# decoder.net
KiCad netlist of a schematic drawn in EAGLE
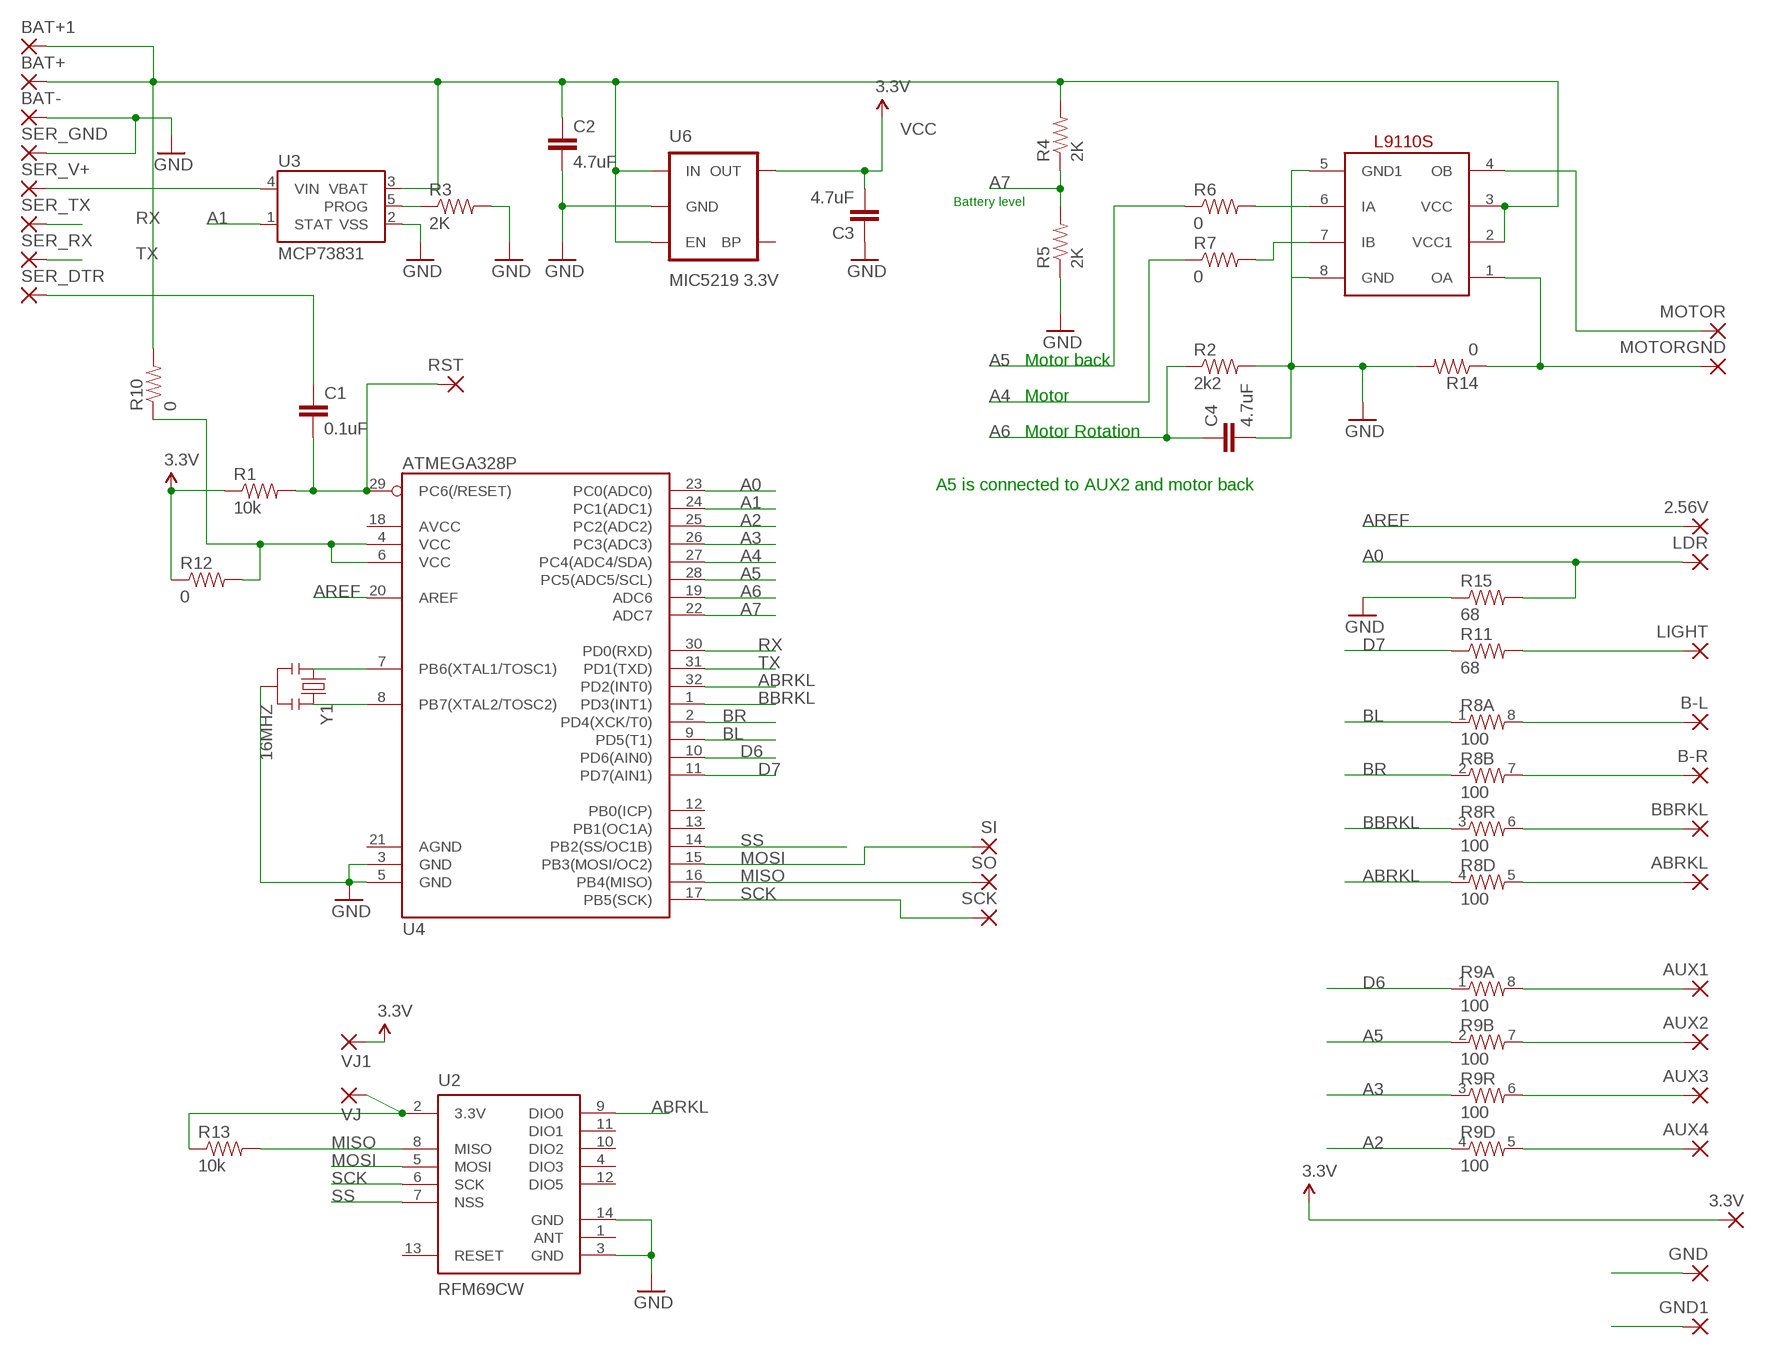
[diagram p0: schematic, sheet 1]

(export (version "E")
  (design (tool "Eeschema 10.0.6"))
  (components
    (comp (ref "2.56V")
      (value "SMD2")
      (footprint "eagle-import:SMD1,27-2,54")
      (libsource (lib "eagle-import") (part "SMD2"))
    )
    (comp (ref "3.3V")
      (value "SMD2")
      (footprint "eagle-import:SMD1,27-2,54")
      (libsource (lib "eagle-import") (part "SMD2"))
    )
    (comp (ref "ABRKL")
      (value "SMD2")
      (footprint "eagle-import:SMD1,27-2,54")
      (libsource (lib "eagle-import") (part "SMD2"))
    )
    (comp (ref "AUX1")
      (value "SMD2")
      (footprint "eagle-import:SMD1,27-2,54")
      (libsource (lib "eagle-import") (part "SMD2"))
    )
    (comp (ref "AUX2")
      (value "SMD2")
      (footprint "eagle-import:SMD1,27-2,54")
      (libsource (lib "eagle-import") (part "SMD2"))
    )
    (comp (ref "AUX3")
      (value "SMD2")
      (footprint "eagle-import:SMD1,27-2,54")
      (libsource (lib "eagle-import") (part "SMD2"))
    )
    (comp (ref "AUX4")
      (value "SMD2")
      (footprint "eagle-import:SMD1,27-2,54")
      (libsource (lib "eagle-import") (part "SMD2"))
    )
    (comp (ref "B-L")
      (value "SMD2")
      (footprint "eagle-import:SMD1,27-2,54")
      (libsource (lib "eagle-import") (part "SMD2"))
    )
    (comp (ref "B-R")
      (value "SMD2")
      (footprint "eagle-import:SMD1,27-2,54")
      (libsource (lib "eagle-import") (part "SMD2"))
    )
    (comp (ref "BAT+")
      (value "SMD2")
      (footprint "eagle-import:SMD1,27-2,54")
      (libsource (lib "eagle-import") (part "SMD2"))
    )
    (comp (ref "BAT+1")
      (value "SMD2")
      (footprint "eagle-import:SMD1,27-2,54")
      (libsource (lib "eagle-import") (part "SMD2"))
    )
    (comp (ref "BAT-")
      (value "SMD2")
      (footprint "eagle-import:SMD1,27-2,54")
      (libsource (lib "eagle-import") (part "SMD2"))
    )
    (comp (ref "BBRKL")
      (value "SMD2")
      (footprint "eagle-import:SMD1,27-2,54")
      (libsource (lib "eagle-import") (part "SMD2"))
    )
    (comp (ref "C1")
      (value "0.1uF")
      (footprint "eagle-import:0805")
      (libsource (lib "eagle-import") (part "CAP0805"))
    )
    (comp (ref "C2")
      (value "4.7uF")
      (footprint "eagle-import:0805")
      (libsource (lib "eagle-import") (part "CAP0805"))
    )
    (comp (ref "C3")
      (value "4.7uF")
      (footprint "eagle-import:0805")
      (libsource (lib "eagle-import") (part "CAP0805"))
    )
    (comp (ref "C4")
      (value "4.7uF")
      (footprint "eagle-import:0805")
      (libsource (lib "eagle-import") (part "CAP0805"))
    )
    (comp (ref "GND")
      (value "SMD2")
      (footprint "eagle-import:SMD1,27-2,54")
      (libsource (lib "eagle-import") (part "SMD2"))
    )
    (comp (ref "GND1")
      (value "SMD2")
      (footprint "eagle-import:SMD1,27-2,54")
      (libsource (lib "eagle-import") (part "SMD2"))
    )
    (comp (ref "LDR")
      (value "SMD2")
      (footprint "eagle-import:SMD1,27-2,54")
      (libsource (lib "eagle-import") (part "SMD2"))
    )
    (comp (ref "LIGHT")
      (value "SMD2")
      (footprint "eagle-import:SMD1,27-2,54")
      (libsource (lib "eagle-import") (part "SMD2"))
    )
    (comp (ref "MDRIVER")
      (value "L9110S")
      (footprint "eagle-import:SO08")
      (libsource (lib "eagle-import") (part "L9110S"))
    )
    (comp (ref "MOTOR")
      (value "SMD2")
      (footprint "eagle-import:SMD1,27-2,54")
      (libsource (lib "eagle-import") (part "SMD2"))
    )
    (comp (ref "MOTORGND")
      (value "SMD2")
      (footprint "eagle-import:SMD1,27-2,54")
      (libsource (lib "eagle-import") (part "SMD2"))
    )
    (comp (ref "R1")
      (value "10k")
      (footprint "eagle-import:0603-RES")
      (libsource (lib "eagle-import") (part "RESISTOR0603-RES"))
    )
    (comp (ref "R2")
      (value "2k2")
      (footprint "eagle-import:0603-RES")
      (libsource (lib "eagle-import") (part "RESISTOR0603-RES"))
    )
    (comp (ref "R3")
      (value "2K")
      (footprint "eagle-import:0603-RES")
      (libsource (lib "eagle-import") (part "RESISTOR0603-RES"))
    )
    (comp (ref "R4")
      (value "2K")
      (footprint "eagle-import:0603-RES")
      (libsource (lib "eagle-import") (part "RESISTOR0603-RES"))
    )
    (comp (ref "R5")
      (value "2K")
      (footprint "eagle-import:0603-RES")
      (libsource (lib "eagle-import") (part "RESISTOR0603-RES"))
    )
    (comp (ref "R6")
      (value "0")
      (footprint "eagle-import:0603-RES")
      (libsource (lib "eagle-import") (part "RESISTOR0603-RES"))
    )
    (comp (ref "R7")
      (value "0")
      (footprint "eagle-import:0603-RES")
      (libsource (lib "eagle-import") (part "RESISTOR0603-RES"))
    )
    (comp (ref "R8")
      (value "100")
      (footprint "eagle-import:0603-ARV")
      (libsource (lib "eagle-import") (part "RESISTOR-ARRAY0603-ARV"))
    )
    (comp (ref "R9")
      (value "100")
      (footprint "eagle-import:0603-ARV")
      (libsource (lib "eagle-import") (part "RESISTOR-ARRAY0603-ARV"))
    )
    (comp (ref "R10")
      (value "0")
      (footprint "eagle-import:0603-RES")
      (libsource (lib "eagle-import") (part "RESISTOR0603-RES"))
    )
    (comp (ref "R11")
      (value "68")
      (footprint "eagle-import:0603-RES")
      (libsource (lib "eagle-import") (part "RESISTOR0603-RES"))
    )
    (comp (ref "R12")
      (value "0")
      (footprint "eagle-import:0603-RES")
      (libsource (lib "eagle-import") (part "RESISTOR0603-RES"))
    )
    (comp (ref "R13")
      (value "10k")
      (footprint "eagle-import:0603-RES")
      (libsource (lib "eagle-import") (part "RESISTOR0603-RES"))
    )
    (comp (ref "R14")
      (value "0")
      (footprint "eagle-import:0603-RES")
      (libsource (lib "eagle-import") (part "RESISTOR0603-RES"))
    )
    (comp (ref "R15")
      (value "68")
      (footprint "eagle-import:0603-RES")
      (libsource (lib "eagle-import") (part "RESISTOR0603-RES"))
    )
    (comp (ref "RST")
      (value "SMD2")
      (footprint "eagle-import:SMD1,27-2,54")
      (libsource (lib "eagle-import") (part "SMD2"))
    )
    (comp (ref "SCK")
      (value "SMD2")
      (footprint "eagle-import:SMD1,27-2,54")
      (libsource (lib "eagle-import") (part "SMD2"))
    )
    (comp (ref "SER_DTR")
      (value "SMD2")
      (footprint "eagle-import:SMD1,27-2,54")
      (libsource (lib "eagle-import") (part "SMD2"))
    )
    (comp (ref "SER_GND")
      (value "SMD2")
      (footprint "eagle-import:SMD1,27-2,54")
      (libsource (lib "eagle-import") (part "SMD2"))
    )
    (comp (ref "SER_RX")
      (value "SMD2")
      (footprint "eagle-import:SMD1,27-2,54")
      (libsource (lib "eagle-import") (part "SMD2"))
    )
    (comp (ref "SER_TX")
      (value "SMD2")
      (footprint "eagle-import:SMD1,27-2,54")
      (libsource (lib "eagle-import") (part "SMD2"))
    )
    (comp (ref "SER_V+")
      (value "SMD2")
      (footprint "eagle-import:SMD1,27-2,54")
      (libsource (lib "eagle-import") (part "SMD2"))
    )
    (comp (ref "SI")
      (value "SMD2")
      (footprint "eagle-import:SMD1,27-2,54")
      (libsource (lib "eagle-import") (part "SMD2"))
    )
    (comp (ref "SO")
      (value "SMD2")
      (footprint "eagle-import:SMD1,27-2,54")
      (libsource (lib "eagle-import") (part "SMD2"))
    )
    (comp (ref "U2")
      (value "RFM69CW")
      (footprint "eagle-import:RFM69CW-XXXS2")
      (libsource (lib "eagle-import") (part "RFM69CW"))
    )
    (comp (ref "U3")
      (value "MCP73831")
      (footprint "eagle-import:SOT23-5")
      (libsource (lib "eagle-import") (part "MCP73831"))
    )
    (comp (ref "U4")
      (value "ATMEGA328P")
      (footprint "eagle-import:TQFP32-08")
      (libsource (lib "eagle-import") (part "ATMEGA328_SMT"))
    )
    (comp (ref "U6")
      (value "MIC5219 3.3V")
      (footprint "eagle-import:SOT23-5")
      (libsource (lib "eagle-import") (part "V_REG_MIC52193.3V"))
    )
    (comp (ref "VJ")
      (value "SMD2")
      (footprint "eagle-import:SMD1,27-2,54")
      (libsource (lib "eagle-import") (part "SMD2"))
    )
    (comp (ref "VJ1")
      (value "SMD2")
      (footprint "eagle-import:SMD1,27-2,54")
      (libsource (lib "eagle-import") (part "SMD2"))
    )
    (comp (ref "Y1")
      (value "16MHZ")
      (footprint "eagle-import:RESONATOR-SMD")
      (libsource (lib "eagle-import") (part "RESONATOR16MHZ"))
    )
  )
  (nets
    (net (code "1") (name "/A0") (class "Default")
      (node (ref "LDR") (pin "1") (pinfunction "P_1") (pintype "passive"))
      (node (ref "R15") (pin "2") (pinfunction "2_2") (pintype "passive"))
      (node (ref "U4") (pin "23") (pinfunction "PC0(ADC0)_23") (pintype "bidirectional"))
    )
    (net (code "2") (name "/A1") (class "Default")
      (node (ref "U3") (pin "1") (pinfunction "STAT_1") (pintype "output"))
      (node (ref "U4") (pin "24") (pinfunction "PC1(ADC1)_24") (pintype "bidirectional"))
    )
    (net (code "3") (name "/A2") (class "Default")
      (node (ref "R9") (pin "4") (pinfunction "1_4") (pintype "passive"))
      (node (ref "U4") (pin "25") (pinfunction "PC2(ADC2)_25") (pintype "bidirectional"))
    )
    (net (code "4") (name "/A3") (class "Default")
      (node (ref "R9") (pin "3") (pinfunction "1_3") (pintype "passive"))
      (node (ref "U4") (pin "26") (pinfunction "PC3(ADC3)_26") (pintype "bidirectional"))
    )
    (net (code "5") (name "/A4") (class "Default")
      (node (ref "R7") (pin "1") (pinfunction "1_1") (pintype "passive"))
      (node (ref "U4") (pin "27") (pinfunction "PC4(ADC4/SDA)_27") (pintype "bidirectional"))
    )
    (net (code "6") (name "/A5") (class "Default")
      (node (ref "R6") (pin "1") (pinfunction "1_1") (pintype "passive"))
      (node (ref "R9") (pin "2") (pinfunction "1_2") (pintype "passive"))
      (node (ref "U4") (pin "28") (pinfunction "PC5(ADC5/SCL)_28") (pintype "bidirectional"))
    )
    (net (code "7") (name "/A6") (class "Default")
      (node (ref "C4") (pin "1") (pinfunction "1_1") (pintype "passive"))
      (node (ref "R2") (pin "1") (pinfunction "1_1") (pintype "passive"))
      (node (ref "U4") (pin "19") (pinfunction "ADC6_19") (pintype "bidirectional"))
    )
    (net (code "8") (name "/A7") (class "Default")
      (node (ref "R4") (pin "1") (pinfunction "1_1") (pintype "passive"))
      (node (ref "R5") (pin "2") (pinfunction "2_2") (pintype "passive"))
      (node (ref "U4") (pin "22") (pinfunction "ADC7_22") (pintype "bidirectional"))
    )
    (net (code "9") (name "/ABRKL") (class "Default")
      (node (ref "R8") (pin "4") (pinfunction "1_4") (pintype "passive"))
      (node (ref "U2") (pin "9") (pinfunction "DIO0_9") (pintype "bidirectional"))
      (node (ref "U4") (pin "32") (pinfunction "PD2(INT0)_32") (pintype "bidirectional"))
    )
    (net (code "10") (name "/AREF") (class "Default")
      (node (ref "2.56V") (pin "1") (pinfunction "P_1") (pintype "passive"))
      (node (ref "U4") (pin "20") (pinfunction "AREF_20") (pintype "bidirectional"))
    )
    (net (code "11") (name "/BBRKL") (class "Default")
      (node (ref "R8") (pin "3") (pinfunction "1_3") (pintype "passive"))
      (node (ref "U4") (pin "1") (pinfunction "PD3(INT1)_1") (pintype "bidirectional"))
    )
    (net (code "12") (name "/BL") (class "Default")
      (node (ref "R8") (pin "1") (pinfunction "1_1") (pintype "passive"))
      (node (ref "U4") (pin "9") (pinfunction "PD5(T1)_9") (pintype "bidirectional"))
    )
    (net (code "13") (name "/BR") (class "Default")
      (node (ref "R8") (pin "2") (pinfunction "1_2") (pintype "passive"))
      (node (ref "U4") (pin "2") (pinfunction "PD4(XCK/T0)_2") (pintype "bidirectional"))
    )
    (net (code "14") (name "/D6") (class "Default")
      (node (ref "R9") (pin "1") (pinfunction "1_1") (pintype "passive"))
      (node (ref "U4") (pin "10") (pinfunction "PD6(AIN0)_10") (pintype "bidirectional"))
    )
    (net (code "15") (name "/D7") (class "Default")
      (node (ref "R11") (pin "1") (pinfunction "1_1") (pintype "passive"))
      (node (ref "U4") (pin "11") (pinfunction "PD7(AIN1)_11") (pintype "bidirectional"))
    )
    (net (code "16") (name "/MISO") (class "Default")
      (node (ref "R13") (pin "2") (pinfunction "2_2") (pintype "passive"))
      (node (ref "SO") (pin "1") (pinfunction "P_1") (pintype "passive"))
      (node (ref "U2") (pin "8") (pinfunction "MISO_8") (pintype "bidirectional"))
      (node (ref "U4") (pin "16") (pinfunction "PB4(MISO)_16") (pintype "bidirectional"))
    )
    (net (code "17") (name "/MOSI") (class "Default")
      (node (ref "SI") (pin "1") (pinfunction "P_1") (pintype "passive"))
      (node (ref "U2") (pin "5") (pinfunction "MOSI_5") (pintype "input"))
      (node (ref "U4") (pin "15") (pinfunction "PB3(MOSI/OC2)_15") (pintype "bidirectional"))
    )
    (net (code "18") (name "/RX") (class "Default")
      (node (ref "SER_TX") (pin "1") (pinfunction "P_1") (pintype "passive"))
      (node (ref "U4") (pin "30") (pinfunction "PD0(RXD)_30") (pintype "bidirectional"))
    )
    (net (code "19") (name "/SCK") (class "Default")
      (node (ref "SCK") (pin "1") (pinfunction "P_1") (pintype "passive"))
      (node (ref "U2") (pin "6") (pinfunction "SCK_6") (pintype "input"))
      (node (ref "U4") (pin "17") (pinfunction "PB5(SCK)_17") (pintype "bidirectional"))
    )
    (net (code "20") (name "/SS") (class "Default")
      (node (ref "U2") (pin "7") (pinfunction "NSS_7") (pintype "input"))
      (node (ref "U4") (pin "14") (pinfunction "PB2(SS/OC1B)_14") (pintype "bidirectional"))
    )
    (net (code "21") (name "/TX") (class "Default")
      (node (ref "SER_RX") (pin "1") (pinfunction "P_1") (pintype "passive"))
      (node (ref "U4") (pin "31") (pinfunction "PD1(TXD)_31") (pintype "bidirectional"))
    )
    (net (code "22") (name "3.3V") (class "Default")
      (node (ref "3.3V") (pin "1") (pinfunction "P_1") (pintype "passive"))
      (node (ref "C3") (pin "2") (pinfunction "2_2") (pintype "passive"))
      (node (ref "R1") (pin "1") (pinfunction "1_1") (pintype "passive"))
      (node (ref "R12") (pin "1") (pinfunction "1_1") (pintype "passive"))
      (node (ref "U6") (pin "5") (pinfunction "OUT_5") (pintype "passive"))
      (node (ref "VJ1") (pin "1") (pinfunction "P_1") (pintype "passive"))
    )
    (net (code "23") (name "GND") (class "Default")
      (node (ref "BAT-") (pin "1") (pinfunction "P_1") (pintype "passive"))
      (node (ref "C2") (pin "2") (pinfunction "2_2") (pintype "passive"))
      (node (ref "C3") (pin "1") (pinfunction "1_1") (pintype "passive"))
      (node (ref "C4") (pin "2") (pinfunction "2_2") (pintype "passive"))
      (node (ref "GND") (pin "1") (pinfunction "P_1") (pintype "passive"))
      (node (ref "GND1") (pin "1") (pinfunction "P_1") (pintype "passive"))
      (node (ref "MDRIVER") (pin "5") (pinfunction "GND1_5") (pintype "passive"))
      (node (ref "MDRIVER") (pin "8") (pinfunction "GND_8") (pintype "output"))
      (node (ref "R14") (pin "2") (pinfunction "2_2") (pintype "passive"))
      (node (ref "R15") (pin "1") (pinfunction "1_1") (pintype "passive"))
      (node (ref "R2") (pin "2") (pinfunction "2_2") (pintype "passive"))
      (node (ref "R3") (pin "2") (pinfunction "2_2") (pintype "passive"))
      (node (ref "R5") (pin "1") (pinfunction "1_1") (pintype "passive"))
      (node (ref "SER_GND") (pin "1") (pinfunction "P_1") (pintype "passive"))
      (node (ref "U2") (pin "14") (pinfunction "GND_14") (pintype "power_in"))
      (node (ref "U2") (pin "3") (pinfunction "GND_3") (pintype "power_in"))
      (node (ref "U3") (pin "2") (pinfunction "VSS_2") (pintype "power_in"))
      (node (ref "U4") (pin "3") (pinfunction "GND_3") (pintype "bidirectional"))
      (node (ref "U4") (pin "5") (pinfunction "GND_5") (pintype "bidirectional"))
      (node (ref "U6") (pin "2") (pinfunction "GND_2") (pintype "input"))
      (node (ref "Y1") (pin "2") (pinfunction "2_2") (pintype "passive"))
    )
    (net (code "24") (name "Net-(ABRKL-P)") (class "Default")
      (node (ref "ABRKL") (pin "1") (pinfunction "P_1") (pintype "passive"))
      (node (ref "R8") (pin "5") (pinfunction "2_5") (pintype "passive"))
    )
    (net (code "25") (name "Net-(AUX1-P)") (class "Default")
      (node (ref "AUX1") (pin "1") (pinfunction "P_1") (pintype "passive"))
      (node (ref "R9") (pin "8") (pinfunction "2_8") (pintype "passive"))
    )
    (net (code "26") (name "Net-(AUX2-P)") (class "Default")
      (node (ref "AUX2") (pin "1") (pinfunction "P_1") (pintype "passive"))
      (node (ref "R9") (pin "7") (pinfunction "2_7") (pintype "passive"))
    )
    (net (code "27") (name "Net-(AUX3-P)") (class "Default")
      (node (ref "AUX3") (pin "1") (pinfunction "P_1") (pintype "passive"))
      (node (ref "R9") (pin "6") (pinfunction "2_6") (pintype "passive"))
    )
    (net (code "28") (name "Net-(AUX4-P)") (class "Default")
      (node (ref "AUX4") (pin "1") (pinfunction "P_1") (pintype "passive"))
      (node (ref "R9") (pin "5") (pinfunction "2_5") (pintype "passive"))
    )
    (net (code "29") (name "Net-(B-L-P)") (class "Default")
      (node (ref "B-L") (pin "1") (pinfunction "P_1") (pintype "passive"))
      (node (ref "R8") (pin "8") (pinfunction "2_8") (pintype "passive"))
    )
    (net (code "30") (name "Net-(B-R-P)") (class "Default")
      (node (ref "B-R") (pin "1") (pinfunction "P_1") (pintype "passive"))
      (node (ref "R8") (pin "7") (pinfunction "2_7") (pintype "passive"))
    )
    (net (code "31") (name "Net-(BAT+-P)") (class "Default")
      (node (ref "BAT+") (pin "1") (pinfunction "P_1") (pintype "passive"))
      (node (ref "BAT+1") (pin "1") (pinfunction "P_1") (pintype "passive"))
      (node (ref "C2") (pin "1") (pinfunction "1_1") (pintype "passive"))
      (node (ref "MDRIVER") (pin "2") (pinfunction "VCC1_2") (pintype "input"))
      (node (ref "MDRIVER") (pin "3") (pinfunction "VCC_3") (pintype "input"))
      (node (ref "R10") (pin "2") (pinfunction "2_2") (pintype "passive"))
      (node (ref "R4") (pin "2") (pinfunction "2_2") (pintype "passive"))
      (node (ref "U3") (pin "3") (pinfunction "VBAT_3") (pintype "power_in"))
      (node (ref "U6") (pin "1") (pinfunction "IN_1") (pintype "input"))
      (node (ref "U6") (pin "3") (pinfunction "EN_3") (pintype "input"))
    )
    (net (code "32") (name "Net-(BBRKL-P)") (class "Default")
      (node (ref "BBRKL") (pin "1") (pinfunction "P_1") (pintype "passive"))
      (node (ref "R8") (pin "6") (pinfunction "2_6") (pintype "passive"))
    )
    (net (code "33") (name "Net-(LIGHT-P)") (class "Default")
      (node (ref "LIGHT") (pin "1") (pinfunction "P_1") (pintype "passive"))
      (node (ref "R11") (pin "2") (pinfunction "2_2") (pintype "passive"))
    )
    (net (code "34") (name "Net-(MDRIVER-IA)") (class "Default")
      (node (ref "MDRIVER") (pin "6") (pinfunction "IA_6") (pintype "passive"))
      (node (ref "R6") (pin "2") (pinfunction "2_2") (pintype "passive"))
    )
    (net (code "35") (name "Net-(MDRIVER-IB)") (class "Default")
      (node (ref "MDRIVER") (pin "7") (pinfunction "IB_7") (pintype "output"))
      (node (ref "R7") (pin "2") (pinfunction "2_2") (pintype "passive"))
    )
    (net (code "36") (name "Net-(MDRIVER-OA)") (class "Default")
      (node (ref "MDRIVER") (pin "1") (pinfunction "OA_1") (pintype "power_in"))
      (node (ref "MOTORGND") (pin "1") (pinfunction "P_1") (pintype "passive"))
      (node (ref "R14") (pin "1") (pinfunction "1_1") (pintype "passive"))
    )
    (net (code "37") (name "Net-(MDRIVER-OB)") (class "Default")
      (node (ref "MDRIVER") (pin "4") (pinfunction "OB_4") (pintype "power_in"))
      (node (ref "MOTOR") (pin "1") (pinfunction "P_1") (pintype "passive"))
    )
    (net (code "38") (name "Net-(R10-Pad1)") (class "Default")
      (node (ref "R10") (pin "1") (pinfunction "1_1") (pintype "passive"))
      (node (ref "R12") (pin "2") (pinfunction "2_2") (pintype "passive"))
      (node (ref "U4") (pin "4") (pinfunction "VCC_4") (pintype "bidirectional"))
      (node (ref "U4") (pin "6") (pinfunction "VCC_6") (pintype "bidirectional"))
    )
    (net (code "39") (name "Net-(RST-P)") (class "Default")
      (node (ref "C1") (pin "2") (pinfunction "2_2") (pintype "passive"))
      (node (ref "R1") (pin "2") (pinfunction "2_2") (pintype "passive"))
      (node (ref "RST") (pin "1") (pinfunction "P_1") (pintype "passive"))
      (node (ref "U4") (pin "29") (pinfunction "PC6(/RESET)_29") (pintype "bidirectional"))
    )
    (net (code "40") (name "Net-(SER_DTR-P)") (class "Default")
      (node (ref "C1") (pin "1") (pinfunction "1_1") (pintype "passive"))
      (node (ref "SER_DTR") (pin "1") (pinfunction "P_1") (pintype "passive"))
    )
    (net (code "41") (name "Net-(SER_V+-P)") (class "Default")
      (node (ref "SER_V+") (pin "1") (pinfunction "P_1") (pintype "passive"))
      (node (ref "U3") (pin "4") (pinfunction "VIN_4") (pintype "power_in"))
    )
    (net (code "42") (name "Net-(U2-3.3V)") (class "Default")
      (node (ref "R13") (pin "1") (pinfunction "1_1") (pintype "passive"))
      (node (ref "U2") (pin "2") (pinfunction "3.3V_2") (pintype "power_in"))
      (node (ref "VJ") (pin "1") (pinfunction "P_1") (pintype "passive"))
    )
    (net (code "43") (name "Net-(U3-PROG)") (class "Default")
      (node (ref "R3") (pin "1") (pinfunction "1_1") (pintype "passive"))
      (node (ref "U3") (pin "5") (pinfunction "PROG_5") (pintype "input"))
    )
    (net (code "44") (name "Net-(U4-PB6(XTAL1{slash}TOSC1))") (class "Default")
      (node (ref "U4") (pin "7") (pinfunction "PB6(XTAL1/TOSC1)_7") (pintype "bidirectional"))
      (node (ref "Y1") (pin "1") (pinfunction "1_1") (pintype "passive"))
    )
    (net (code "45") (name "Net-(U4-PB7(XTAL2{slash}TOSC2))") (class "Default")
      (node (ref "U4") (pin "8") (pinfunction "PB7(XTAL2/TOSC2)_8") (pintype "bidirectional"))
      (node (ref "Y1") (pin "3") (pinfunction "3_3") (pintype "passive"))
    )
    (net (code "46") (name "unconnected-(U2-ANT-Pad1)") (class "Default")
      (node (ref "U2") (pin "1") (pinfunction "ANT_1") (pintype "passive"))
    )
    (net (code "47") (name "unconnected-(U2-DIO1-Pad11)") (class "Default")
      (node (ref "U2") (pin "11") (pinfunction "DIO1_11") (pintype "bidirectional"))
    )
    (net (code "48") (name "unconnected-(U2-DIO2-Pad10)") (class "Default")
      (node (ref "U2") (pin "10") (pinfunction "DIO2_10") (pintype "bidirectional"))
    )
    (net (code "49") (name "unconnected-(U2-DIO3-Pad4)") (class "Default")
      (node (ref "U2") (pin "4") (pinfunction "DIO3_4") (pintype "bidirectional"))
    )
    (net (code "50") (name "unconnected-(U2-DIO5-Pad12)") (class "Default")
      (node (ref "U2") (pin "12") (pinfunction "DIO5_12") (pintype "bidirectional"))
    )
    (net (code "51") (name "unconnected-(U2-RESET-Pad13)") (class "Default")
      (node (ref "U2") (pin "13") (pinfunction "RESET_13") (pintype "input"))
    )
    (net (code "52") (name "unconnected-(U4-AGND-Pad21)") (class "Default")
      (node (ref "U4") (pin "21") (pinfunction "AGND_21") (pintype "bidirectional"))
    )
    (net (code "53") (name "unconnected-(U4-AVCC-Pad18)") (class "Default")
      (node (ref "U4") (pin "18") (pinfunction "AVCC_18") (pintype "bidirectional"))
    )
    (net (code "54") (name "unconnected-(U4-PB0(ICP)-Pad12)") (class "Default")
      (node (ref "U4") (pin "12") (pinfunction "PB0(ICP)_12") (pintype "bidirectional"))
    )
    (net (code "55") (name "unconnected-(U4-PB1(OC1A)-Pad13)") (class "Default")
      (node (ref "U4") (pin "13") (pinfunction "PB1(OC1A)_13") (pintype "bidirectional"))
    )
    (net (code "56") (name "unconnected-(U6-BP-Pad4)") (class "Default")
      (node (ref "U6") (pin "4") (pinfunction "BP_4") (pintype "input"))
    )
  )
)
